# HexStepTroller_REV2auto.net
KiCad netlist of a schematic drawn in EAGLE
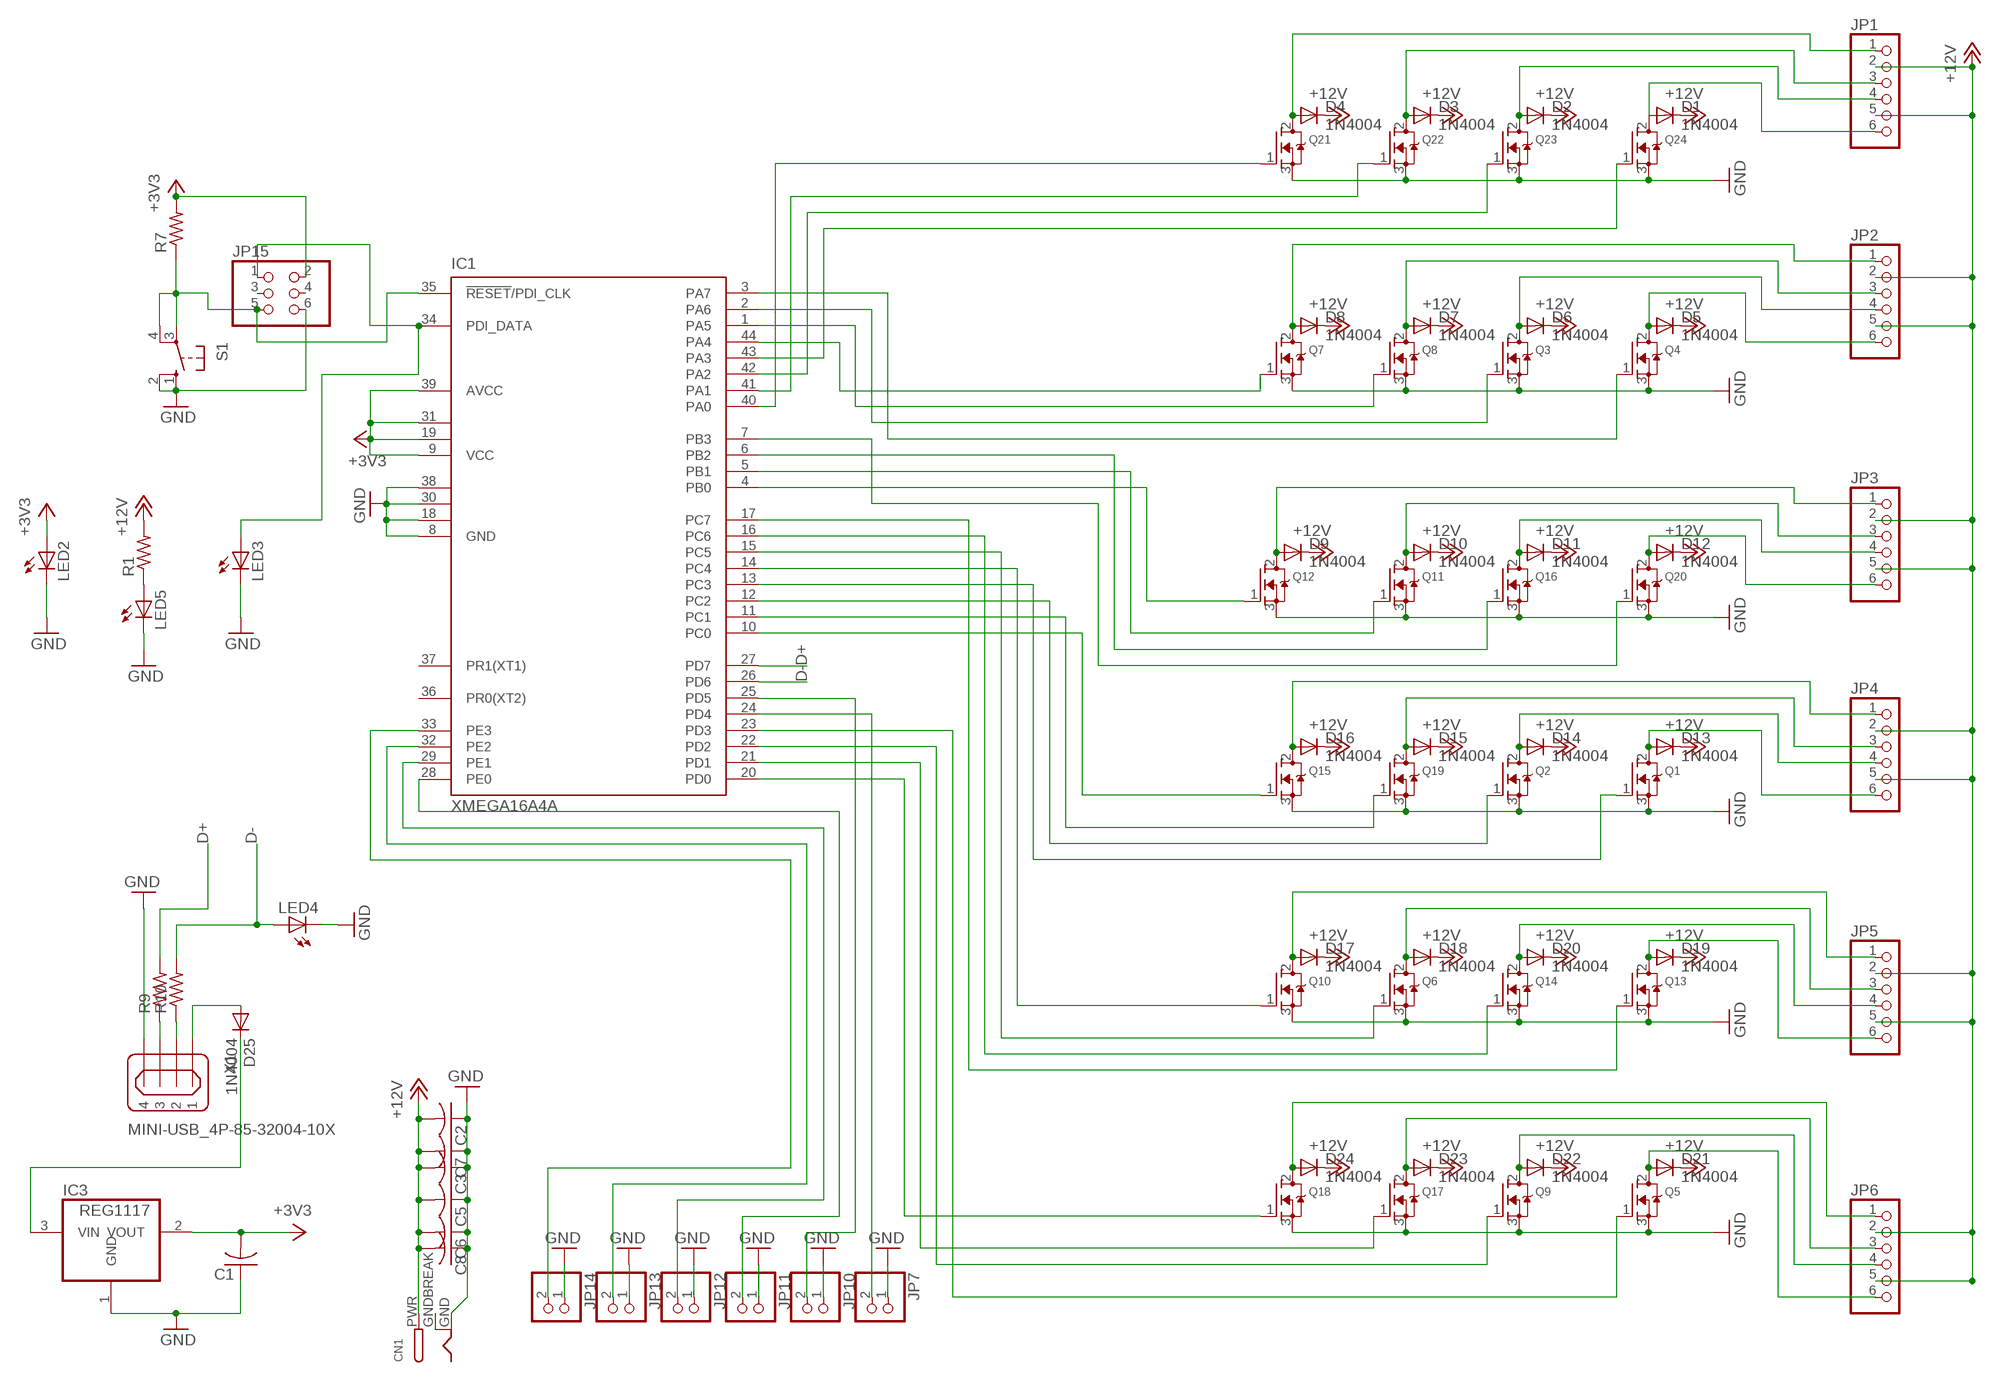
[diagram p0: schematic, sheet 1]

(export (version "E")
  (design (tool "Eeschema 10.0.6"))
  (components
    (comp (ref "C1")
      (value "C-US050-075X075")
      (footprint "eagle-import:C050-075X075")
      (libsource (lib "eagle-import") (part "C-US050-075X075"))
    )
    (comp (ref "C2")
      (value "C-US050-075X075")
      (footprint "eagle-import:C050-075X075")
      (libsource (lib "eagle-import") (part "C-US050-075X075"))
    )
    (comp (ref "C3")
      (value "C-US050-075X075")
      (footprint "eagle-import:C050-075X075")
      (libsource (lib "eagle-import") (part "C-US050-075X075"))
    )
    (comp (ref "C5")
      (value "C-US050-075X075")
      (footprint "eagle-import:C050-075X075")
      (libsource (lib "eagle-import") (part "C-US050-075X075"))
    )
    (comp (ref "C6")
      (value "C-US050-075X075")
      (footprint "eagle-import:C050-075X075")
      (libsource (lib "eagle-import") (part "C-US050-075X075"))
    )
    (comp (ref "C7")
      (value "C-US050-075X075")
      (footprint "eagle-import:C050-075X075")
      (libsource (lib "eagle-import") (part "C-US050-075X075"))
    )
    (comp (ref "C8")
      (value "C-US050-075X075")
      (footprint "eagle-import:C050-075X075")
      (libsource (lib "eagle-import") (part "C-US050-075X075"))
    )
    (comp (ref "CN1")
      (value "DCBARRELPTH")
      (footprint "eagle-import:DCJACK_2MM_PTH")
      (libsource (lib "eagle-import") (part "DCBARRELPTH"))
    )
    (comp (ref "D1")
      (value "1N4004")
      (footprint "eagle-import:DO41-10")
      (libsource (lib "eagle-import") (part "1N4004"))
    )
    (comp (ref "D2")
      (value "1N4004")
      (footprint "eagle-import:DO41-10")
      (libsource (lib "eagle-import") (part "1N4004"))
    )
    (comp (ref "D3")
      (value "1N4004")
      (footprint "eagle-import:DO41-10")
      (libsource (lib "eagle-import") (part "1N4004"))
    )
    (comp (ref "D4")
      (value "1N4004")
      (footprint "eagle-import:DO41-10")
      (libsource (lib "eagle-import") (part "1N4004"))
    )
    (comp (ref "D5")
      (value "1N4004")
      (footprint "eagle-import:DO41-10")
      (libsource (lib "eagle-import") (part "1N4004"))
    )
    (comp (ref "D6")
      (value "1N4004")
      (footprint "eagle-import:DO41-10")
      (libsource (lib "eagle-import") (part "1N4004"))
    )
    (comp (ref "D7")
      (value "1N4004")
      (footprint "eagle-import:DO41-10")
      (libsource (lib "eagle-import") (part "1N4004"))
    )
    (comp (ref "D8")
      (value "1N4004")
      (footprint "eagle-import:DO41-10")
      (libsource (lib "eagle-import") (part "1N4004"))
    )
    (comp (ref "D9")
      (value "1N4004")
      (footprint "eagle-import:DO41-10")
      (libsource (lib "eagle-import") (part "1N4004"))
    )
    (comp (ref "D10")
      (value "1N4004")
      (footprint "eagle-import:DO41-10")
      (libsource (lib "eagle-import") (part "1N4004"))
    )
    (comp (ref "D11")
      (value "1N4004")
      (footprint "eagle-import:DO41-10")
      (libsource (lib "eagle-import") (part "1N4004"))
    )
    (comp (ref "D12")
      (value "1N4004")
      (footprint "eagle-import:DO41-10")
      (libsource (lib "eagle-import") (part "1N4004"))
    )
    (comp (ref "D13")
      (value "1N4004")
      (footprint "eagle-import:DO41-10")
      (libsource (lib "eagle-import") (part "1N4004"))
    )
    (comp (ref "D14")
      (value "1N4004")
      (footprint "eagle-import:DO41-10")
      (libsource (lib "eagle-import") (part "1N4004"))
    )
    (comp (ref "D15")
      (value "1N4004")
      (footprint "eagle-import:DO41-10")
      (libsource (lib "eagle-import") (part "1N4004"))
    )
    (comp (ref "D16")
      (value "1N4004")
      (footprint "eagle-import:DO41-10")
      (libsource (lib "eagle-import") (part "1N4004"))
    )
    (comp (ref "D17")
      (value "1N4004")
      (footprint "eagle-import:DO41-10")
      (libsource (lib "eagle-import") (part "1N4004"))
    )
    (comp (ref "D18")
      (value "1N4004")
      (footprint "eagle-import:DO41-10")
      (libsource (lib "eagle-import") (part "1N4004"))
    )
    (comp (ref "D19")
      (value "1N4004")
      (footprint "eagle-import:DO41-10")
      (libsource (lib "eagle-import") (part "1N4004"))
    )
    (comp (ref "D20")
      (value "1N4004")
      (footprint "eagle-import:DO41-10")
      (libsource (lib "eagle-import") (part "1N4004"))
    )
    (comp (ref "D21")
      (value "1N4004")
      (footprint "eagle-import:DO41-10")
      (libsource (lib "eagle-import") (part "1N4004"))
    )
    (comp (ref "D22")
      (value "1N4004")
      (footprint "eagle-import:DO41-10")
      (libsource (lib "eagle-import") (part "1N4004"))
    )
    (comp (ref "D23")
      (value "1N4004")
      (footprint "eagle-import:DO41-10")
      (libsource (lib "eagle-import") (part "1N4004"))
    )
    (comp (ref "D24")
      (value "1N4004")
      (footprint "eagle-import:DO41-10")
      (libsource (lib "eagle-import") (part "1N4004"))
    )
    (comp (ref "D25")
      (value "1N4004")
      (footprint "eagle-import:DO41-10")
      (libsource (lib "eagle-import") (part "1N4004"))
    )
    (comp (ref "IC1")
      (value "XMEGA16A4A")
      (footprint "eagle-import:TQFP44")
      (libsource (lib "eagle-import") (part "XMEGA16A4A"))
    )
    (comp (ref "IC3")
      (value "REG1117")
      (footprint "eagle-import:SOT223")
      (libsource (lib "eagle-import") (part "REG1117"))
    )
    (comp (ref "JP1")
      (value "PINHD-1X6")
      (footprint "eagle-import:1X06")
      (libsource (lib "eagle-import") (part "PINHD-1X6"))
    )
    (comp (ref "JP2")
      (value "PINHD-1X6")
      (footprint "eagle-import:1X06")
      (libsource (lib "eagle-import") (part "PINHD-1X6"))
    )
    (comp (ref "JP3")
      (value "PINHD-1X6")
      (footprint "eagle-import:1X06")
      (libsource (lib "eagle-import") (part "PINHD-1X6"))
    )
    (comp (ref "JP4")
      (value "PINHD-1X6")
      (footprint "eagle-import:1X06")
      (libsource (lib "eagle-import") (part "PINHD-1X6"))
    )
    (comp (ref "JP5")
      (value "PINHD-1X6")
      (footprint "eagle-import:1X06")
      (libsource (lib "eagle-import") (part "PINHD-1X6"))
    )
    (comp (ref "JP6")
      (value "PINHD-1X6")
      (footprint "eagle-import:1X06")
      (libsource (lib "eagle-import") (part "PINHD-1X6"))
    )
    (comp (ref "JP7")
      (value "PINHD-1X2")
      (footprint "eagle-import:1X02")
      (libsource (lib "eagle-import") (part "PINHD-1X2"))
    )
    (comp (ref "JP10")
      (value "PINHD-1X2")
      (footprint "eagle-import:1X02")
      (libsource (lib "eagle-import") (part "PINHD-1X2"))
    )
    (comp (ref "JP11")
      (value "PINHD-1X2")
      (footprint "eagle-import:1X02")
      (libsource (lib "eagle-import") (part "PINHD-1X2"))
    )
    (comp (ref "JP12")
      (value "PINHD-1X2")
      (footprint "eagle-import:1X02")
      (libsource (lib "eagle-import") (part "PINHD-1X2"))
    )
    (comp (ref "JP13")
      (value "PINHD-1X2")
      (footprint "eagle-import:1X02")
      (libsource (lib "eagle-import") (part "PINHD-1X2"))
    )
    (comp (ref "JP14")
      (value "PINHD-1X2")
      (footprint "eagle-import:1X02")
      (libsource (lib "eagle-import") (part "PINHD-1X2"))
    )
    (comp (ref "JP15")
      (value "PINHD-2X3")
      (footprint "eagle-import:2X03")
      (libsource (lib "eagle-import") (part "PINHD-2X3"))
    )
    (comp (ref "LED2")
      (value "LED5MM")
      (footprint "eagle-import:LED5MM")
      (libsource (lib "eagle-import") (part "LED5MM"))
    )
    (comp (ref "LED3")
      (value "LED5MM")
      (footprint "eagle-import:LED5MM")
      (libsource (lib "eagle-import") (part "LED5MM"))
    )
    (comp (ref "LED4")
      (value "LED5MM")
      (footprint "eagle-import:LED5MM")
      (libsource (lib "eagle-import") (part "LED5MM"))
    )
    (comp (ref "LED5")
      (value "LED5MM")
      (footprint "eagle-import:LED5MM")
      (libsource (lib "eagle-import") (part "LED5MM"))
    )
    (comp (ref "Q1")
      (value "MOSFET-NGDS_TO220V")
      (footprint "eagle-import:TO220V")
      (libsource (lib "eagle-import") (part "MOSFET-NGDS_TO220V"))
    )
    (comp (ref "Q2")
      (value "MOSFET-NGDS_TO220V")
      (footprint "eagle-import:TO220V")
      (libsource (lib "eagle-import") (part "MOSFET-NGDS_TO220V"))
    )
    (comp (ref "Q3")
      (value "MOSFET-NGDS_TO220V")
      (footprint "eagle-import:TO220V")
      (libsource (lib "eagle-import") (part "MOSFET-NGDS_TO220V"))
    )
    (comp (ref "Q4")
      (value "MOSFET-NGDS_TO220V")
      (footprint "eagle-import:TO220V")
      (libsource (lib "eagle-import") (part "MOSFET-NGDS_TO220V"))
    )
    (comp (ref "Q5")
      (value "MOSFET-NGDS_TO220V")
      (footprint "eagle-import:TO220V")
      (libsource (lib "eagle-import") (part "MOSFET-NGDS_TO220V"))
    )
    (comp (ref "Q6")
      (value "MOSFET-NGDS_TO220V")
      (footprint "eagle-import:TO220V")
      (libsource (lib "eagle-import") (part "MOSFET-NGDS_TO220V"))
    )
    (comp (ref "Q7")
      (value "MOSFET-NGDS_TO220V")
      (footprint "eagle-import:TO220V")
      (libsource (lib "eagle-import") (part "MOSFET-NGDS_TO220V"))
    )
    (comp (ref "Q8")
      (value "MOSFET-NGDS_TO220V")
      (footprint "eagle-import:TO220V")
      (libsource (lib "eagle-import") (part "MOSFET-NGDS_TO220V"))
    )
    (comp (ref "Q9")
      (value "MOSFET-NGDS_TO220V")
      (footprint "eagle-import:TO220V")
      (libsource (lib "eagle-import") (part "MOSFET-NGDS_TO220V"))
    )
    (comp (ref "Q10")
      (value "MOSFET-NGDS_TO220V")
      (footprint "eagle-import:TO220V")
      (libsource (lib "eagle-import") (part "MOSFET-NGDS_TO220V"))
    )
    (comp (ref "Q11")
      (value "MOSFET-NGDS_TO220V")
      (footprint "eagle-import:TO220V")
      (libsource (lib "eagle-import") (part "MOSFET-NGDS_TO220V"))
    )
    (comp (ref "Q12")
      (value "MOSFET-NGDS_TO220V")
      (footprint "eagle-import:TO220V")
      (libsource (lib "eagle-import") (part "MOSFET-NGDS_TO220V"))
    )
    (comp (ref "Q13")
      (value "MOSFET-NGDS_TO220V")
      (footprint "eagle-import:TO220V")
      (libsource (lib "eagle-import") (part "MOSFET-NGDS_TO220V"))
    )
    (comp (ref "Q14")
      (value "MOSFET-NGDS_TO220V")
      (footprint "eagle-import:TO220V")
      (libsource (lib "eagle-import") (part "MOSFET-NGDS_TO220V"))
    )
    (comp (ref "Q15")
      (value "MOSFET-NGDS_TO220V")
      (footprint "eagle-import:TO220V")
      (libsource (lib "eagle-import") (part "MOSFET-NGDS_TO220V"))
    )
    (comp (ref "Q16")
      (value "MOSFET-NGDS_TO220V")
      (footprint "eagle-import:TO220V")
      (libsource (lib "eagle-import") (part "MOSFET-NGDS_TO220V"))
    )
    (comp (ref "Q17")
      (value "MOSFET-NGDS_TO220V")
      (footprint "eagle-import:TO220V")
      (libsource (lib "eagle-import") (part "MOSFET-NGDS_TO220V"))
    )
    (comp (ref "Q18")
      (value "MOSFET-NGDS_TO220V")
      (footprint "eagle-import:TO220V")
      (libsource (lib "eagle-import") (part "MOSFET-NGDS_TO220V"))
    )
    (comp (ref "Q19")
      (value "MOSFET-NGDS_TO220V")
      (footprint "eagle-import:TO220V")
      (libsource (lib "eagle-import") (part "MOSFET-NGDS_TO220V"))
    )
    (comp (ref "Q20")
      (value "MOSFET-NGDS_TO220V")
      (footprint "eagle-import:TO220V")
      (libsource (lib "eagle-import") (part "MOSFET-NGDS_TO220V"))
    )
    (comp (ref "Q21")
      (value "MOSFET-NGDS_TO220V")
      (footprint "eagle-import:TO220V")
      (libsource (lib "eagle-import") (part "MOSFET-NGDS_TO220V"))
    )
    (comp (ref "Q22")
      (value "MOSFET-NGDS_TO220V")
      (footprint "eagle-import:TO220V")
      (libsource (lib "eagle-import") (part "MOSFET-NGDS_TO220V"))
    )
    (comp (ref "Q23")
      (value "MOSFET-NGDS_TO220V")
      (footprint "eagle-import:TO220V")
      (libsource (lib "eagle-import") (part "MOSFET-NGDS_TO220V"))
    )
    (comp (ref "Q24")
      (value "MOSFET-NGDS_TO220V")
      (footprint "eagle-import:TO220V")
      (libsource (lib "eagle-import") (part "MOSFET-NGDS_TO220V"))
    )
    (comp (ref "R1")
      (value "R-US_0204/7")
      (footprint "eagle-import:0204_7")
      (libsource (lib "eagle-import") (part "R-US_0204/7"))
    )
    (comp (ref "R7")
      (value "R-US_0204/7")
      (footprint "eagle-import:0204_7")
      (libsource (lib "eagle-import") (part "R-US_0204/7"))
    )
    (comp (ref "R9")
      (value "R-US_0204/7")
      (footprint "eagle-import:0204_7")
      (libsource (lib "eagle-import") (part "R-US_0204/7"))
    )
    (comp (ref "R10")
      (value "R-US_0204/7")
      (footprint "eagle-import:0204_7")
      (libsource (lib "eagle-import") (part "R-US_0204/7"))
    )
    (comp (ref "S1")
      (value "10-XX")
      (footprint "eagle-import:B3F-10XX")
      (fields (field (name "MPN") "B3F-1000"))
      (libsource (lib "eagle-import") (part "10-XX"))
    )
    (comp (ref "X1")
      (value "MINI-USB_4P-85-32004-10X")
      (footprint "eagle-import:85-32004-10X")
      (libsource (lib "eagle-import") (part "MINI-USB_4P-85-32004-10X"))
    )
  )
  (nets
    (net (code "1") (name "+3V3") (class "Default")
      (node (ref "C1") (pin "2") (pinfunction "2_2") (pintype "passive"))
      (node (ref "IC1") (pin "19") (pinfunction "VCC1_19") (pintype "power_in"))
      (node (ref "IC1") (pin "31") (pinfunction "VCC2_31") (pintype "power_in"))
      (node (ref "IC1") (pin "39") (pinfunction "AVCC_39") (pintype "power_in"))
      (node (ref "IC1") (pin "9") (pinfunction "VCC_9") (pintype "power_in"))
      (node (ref "IC3") (pin "2") (pinfunction "VOUT_2") (pintype "output"))
      (node (ref "JP15") (pin "2") (pinfunction "2_2") (pintype "passive"))
      (node (ref "LED2") (pin "A") (pinfunction "A_A") (pintype "passive"))
      (node (ref "R7") (pin "2") (pinfunction "2_2") (pintype "passive"))
    )
    (net (code "2") (name "+12V") (class "Default")
      (node (ref "C2") (pin "2") (pinfunction "2_2") (pintype "passive"))
      (node (ref "C3") (pin "2") (pinfunction "2_2") (pintype "passive"))
      (node (ref "C5") (pin "2") (pinfunction "2_2") (pintype "passive"))
      (node (ref "C6") (pin "2") (pinfunction "2_2") (pintype "passive"))
      (node (ref "C7") (pin "2") (pinfunction "2_2") (pintype "passive"))
      (node (ref "C8") (pin "2") (pinfunction "2_2") (pintype "passive"))
      (node (ref "CN1") (pin "PWR") (pinfunction "PWR_PWR") (pintype "power_in"))
      (node (ref "D1") (pin "C") (pinfunction "C_C") (pintype "passive"))
      (node (ref "D10") (pin "C") (pinfunction "C_C") (pintype "passive"))
      (node (ref "D11") (pin "C") (pinfunction "C_C") (pintype "passive"))
      (node (ref "D12") (pin "C") (pinfunction "C_C") (pintype "passive"))
      (node (ref "D13") (pin "C") (pinfunction "C_C") (pintype "passive"))
      (node (ref "D14") (pin "C") (pinfunction "C_C") (pintype "passive"))
      (node (ref "D15") (pin "C") (pinfunction "C_C") (pintype "passive"))
      (node (ref "D16") (pin "C") (pinfunction "C_C") (pintype "passive"))
      (node (ref "D17") (pin "C") (pinfunction "C_C") (pintype "passive"))
      (node (ref "D18") (pin "C") (pinfunction "C_C") (pintype "passive"))
      (node (ref "D19") (pin "C") (pinfunction "C_C") (pintype "passive"))
      (node (ref "D2") (pin "C") (pinfunction "C_C") (pintype "passive"))
      (node (ref "D20") (pin "C") (pinfunction "C_C") (pintype "passive"))
      (node (ref "D21") (pin "C") (pinfunction "C_C") (pintype "passive"))
      (node (ref "D22") (pin "C") (pinfunction "C_C") (pintype "passive"))
      (node (ref "D23") (pin "C") (pinfunction "C_C") (pintype "passive"))
      (node (ref "D24") (pin "C") (pinfunction "C_C") (pintype "passive"))
      (node (ref "D3") (pin "C") (pinfunction "C_C") (pintype "passive"))
      (node (ref "D4") (pin "C") (pinfunction "C_C") (pintype "passive"))
      (node (ref "D5") (pin "C") (pinfunction "C_C") (pintype "passive"))
      (node (ref "D6") (pin "C") (pinfunction "C_C") (pintype "passive"))
      (node (ref "D7") (pin "C") (pinfunction "C_C") (pintype "passive"))
      (node (ref "D8") (pin "C") (pinfunction "C_C") (pintype "passive"))
      (node (ref "D9") (pin "C") (pinfunction "C_C") (pintype "passive"))
      (node (ref "JP1") (pin "2") (pinfunction "2_2") (pintype "passive"))
      (node (ref "JP1") (pin "5") (pinfunction "5_5") (pintype "passive"))
      (node (ref "JP2") (pin "2") (pinfunction "2_2") (pintype "passive"))
      (node (ref "JP2") (pin "5") (pinfunction "5_5") (pintype "passive"))
      (node (ref "JP3") (pin "2") (pinfunction "2_2") (pintype "passive"))
      (node (ref "JP3") (pin "5") (pinfunction "5_5") (pintype "passive"))
      (node (ref "JP4") (pin "2") (pinfunction "2_2") (pintype "passive"))
      (node (ref "JP4") (pin "5") (pinfunction "5_5") (pintype "passive"))
      (node (ref "JP5") (pin "2") (pinfunction "2_2") (pintype "passive"))
      (node (ref "JP5") (pin "5") (pinfunction "5_5") (pintype "passive"))
      (node (ref "JP6") (pin "2") (pinfunction "2_2") (pintype "passive"))
      (node (ref "JP6") (pin "5") (pinfunction "5_5") (pintype "passive"))
      (node (ref "R1") (pin "2") (pinfunction "2_2") (pintype "passive"))
    )
    (net (code "3") (name "/D+") (class "Default")
      (node (ref "IC1") (pin "27") (pinfunction "PD7_27") (pintype "bidirectional"))
      (node (ref "R9") (pin "2") (pinfunction "2_2") (pintype "passive"))
    )
    (net (code "4") (name "/D-") (class "Default")
      (node (ref "IC1") (pin "26") (pinfunction "PD6_26") (pintype "bidirectional"))
      (node (ref "LED4") (pin "A") (pinfunction "A_A") (pintype "passive"))
      (node (ref "R10") (pin "2") (pinfunction "2_2") (pintype "passive"))
    )
    (net (code "5") (name "/GNDBREAK") (class "Default")
      (node (ref "CN1") (pin "GNDBREAK") (pinfunction "GNDBREAK_GNDBREAK") (pintype "power_in"))
    )
    (net (code "6") (name "GND") (class "Default")
      (node (ref "C1") (pin "1") (pinfunction "1_1") (pintype "passive"))
      (node (ref "C2") (pin "1") (pinfunction "1_1") (pintype "passive"))
      (node (ref "C3") (pin "1") (pinfunction "1_1") (pintype "passive"))
      (node (ref "C5") (pin "1") (pinfunction "1_1") (pintype "passive"))
      (node (ref "C6") (pin "1") (pinfunction "1_1") (pintype "passive"))
      (node (ref "C7") (pin "1") (pinfunction "1_1") (pintype "passive"))
      (node (ref "C8") (pin "1") (pinfunction "1_1") (pintype "passive"))
      (node (ref "CN1") (pin "GND") (pinfunction "GND_GND") (pintype "power_in"))
      (node (ref "IC1") (pin "18") (pinfunction "GND1_18") (pintype "power_in"))
      (node (ref "IC1") (pin "30") (pinfunction "GND2_30") (pintype "power_in"))
      (node (ref "IC1") (pin "38") (pinfunction "GND3_38") (pintype "power_in"))
      (node (ref "IC1") (pin "8") (pinfunction "GND_8") (pintype "power_in"))
      (node (ref "IC3") (pin "1") (pinfunction "GND_1") (pintype "power_in"))
      (node (ref "JP10") (pin "1") (pinfunction "1_1") (pintype "passive"))
      (node (ref "JP11") (pin "1") (pinfunction "1_1") (pintype "passive"))
      (node (ref "JP12") (pin "1") (pinfunction "1_1") (pintype "passive"))
      (node (ref "JP13") (pin "1") (pinfunction "1_1") (pintype "passive"))
      (node (ref "JP14") (pin "1") (pinfunction "1_1") (pintype "passive"))
      (node (ref "JP15") (pin "6") (pinfunction "6_6") (pintype "passive"))
      (node (ref "JP7") (pin "1") (pinfunction "1_1") (pintype "passive"))
      (node (ref "LED2") (pin "K") (pinfunction "C_K") (pintype "passive"))
      (node (ref "LED3") (pin "K") (pinfunction "C_K") (pintype "passive"))
      (node (ref "LED4") (pin "K") (pinfunction "C_K") (pintype "passive"))
      (node (ref "LED5") (pin "K") (pinfunction "C_K") (pintype "passive"))
      (node (ref "Q1") (pin "3") (pinfunction "S_3") (pintype "bidirectional"))
      (node (ref "Q10") (pin "3") (pinfunction "S_3") (pintype "bidirectional"))
      (node (ref "Q11") (pin "3") (pinfunction "S_3") (pintype "bidirectional"))
      (node (ref "Q12") (pin "3") (pinfunction "S_3") (pintype "bidirectional"))
      (node (ref "Q13") (pin "3") (pinfunction "S_3") (pintype "bidirectional"))
      (node (ref "Q14") (pin "3") (pinfunction "S_3") (pintype "bidirectional"))
      (node (ref "Q15") (pin "3") (pinfunction "S_3") (pintype "bidirectional"))
      (node (ref "Q16") (pin "3") (pinfunction "S_3") (pintype "bidirectional"))
      (node (ref "Q17") (pin "3") (pinfunction "S_3") (pintype "bidirectional"))
      (node (ref "Q18") (pin "3") (pinfunction "S_3") (pintype "bidirectional"))
      (node (ref "Q19") (pin "3") (pinfunction "S_3") (pintype "bidirectional"))
      (node (ref "Q2") (pin "3") (pinfunction "S_3") (pintype "bidirectional"))
      (node (ref "Q20") (pin "3") (pinfunction "S_3") (pintype "bidirectional"))
      (node (ref "Q21") (pin "3") (pinfunction "S_3") (pintype "bidirectional"))
      (node (ref "Q22") (pin "3") (pinfunction "S_3") (pintype "bidirectional"))
      (node (ref "Q23") (pin "3") (pinfunction "S_3") (pintype "bidirectional"))
      (node (ref "Q24") (pin "3") (pinfunction "S_3") (pintype "bidirectional"))
      (node (ref "Q3") (pin "3") (pinfunction "S_3") (pintype "bidirectional"))
      (node (ref "Q4") (pin "3") (pinfunction "S_3") (pintype "bidirectional"))
      (node (ref "Q5") (pin "3") (pinfunction "S_3") (pintype "bidirectional"))
      (node (ref "Q6") (pin "3") (pinfunction "S_3") (pintype "bidirectional"))
      (node (ref "Q7") (pin "3") (pinfunction "S_3") (pintype "bidirectional"))
      (node (ref "Q8") (pin "3") (pinfunction "S_3") (pintype "bidirectional"))
      (node (ref "Q9") (pin "3") (pinfunction "S_3") (pintype "bidirectional"))
      (node (ref "S1") (pin "1") (pinfunction "S_1") (pintype "passive"))
      (node (ref "S1") (pin "2") (pinfunction "S1_2") (pintype "passive"))
      (node (ref "X1") (pin "4") (pinfunction "4_4") (pintype "passive"))
    )
    (net (code "7") (name "Net-(D25-PadA)") (class "Default")
      (node (ref "D25") (pin "A") (pinfunction "A_A") (pintype "passive"))
      (node (ref "X1") (pin "1") (pinfunction "1_1") (pintype "passive"))
    )
    (net (code "8") (name "Net-(IC1-PA0)") (class "Default")
      (node (ref "IC1") (pin "40") (pinfunction "PA0_40") (pintype "bidirectional"))
      (node (ref "Q21") (pin "1") (pinfunction "G_1") (pintype "bidirectional"))
    )
    (net (code "9") (name "Net-(IC1-PA1)") (class "Default")
      (node (ref "IC1") (pin "41") (pinfunction "PA1_41") (pintype "bidirectional"))
      (node (ref "Q22") (pin "1") (pinfunction "G_1") (pintype "bidirectional"))
    )
    (net (code "10") (name "Net-(IC1-PA2)") (class "Default")
      (node (ref "IC1") (pin "42") (pinfunction "PA2_42") (pintype "bidirectional"))
      (node (ref "Q23") (pin "1") (pinfunction "G_1") (pintype "bidirectional"))
    )
    (net (code "11") (name "Net-(IC1-PA3)") (class "Default")
      (node (ref "IC1") (pin "43") (pinfunction "PA3_43") (pintype "bidirectional"))
      (node (ref "Q24") (pin "1") (pinfunction "G_1") (pintype "bidirectional"))
    )
    (net (code "12") (name "Net-(IC1-PA4)") (class "Default")
      (node (ref "IC1") (pin "44") (pinfunction "PA4_44") (pintype "bidirectional"))
      (node (ref "Q7") (pin "1") (pinfunction "G_1") (pintype "bidirectional"))
    )
    (net (code "13") (name "Net-(IC1-PA5)") (class "Default")
      (node (ref "IC1") (pin "1") (pinfunction "PA5_1") (pintype "bidirectional"))
      (node (ref "Q8") (pin "1") (pinfunction "G_1") (pintype "bidirectional"))
    )
    (net (code "14") (name "Net-(IC1-PA6)") (class "Default")
      (node (ref "IC1") (pin "2") (pinfunction "PA6_2") (pintype "bidirectional"))
      (node (ref "Q3") (pin "1") (pinfunction "G_1") (pintype "bidirectional"))
    )
    (net (code "15") (name "Net-(IC1-PA7)") (class "Default")
      (node (ref "IC1") (pin "3") (pinfunction "PA7_3") (pintype "bidirectional"))
      (node (ref "Q4") (pin "1") (pinfunction "G_1") (pintype "bidirectional"))
    )
    (net (code "16") (name "Net-(IC1-PB0)") (class "Default")
      (node (ref "IC1") (pin "4") (pinfunction "PB0_4") (pintype "bidirectional"))
      (node (ref "Q12") (pin "1") (pinfunction "G_1") (pintype "bidirectional"))
    )
    (net (code "17") (name "Net-(IC1-PB1)") (class "Default")
      (node (ref "IC1") (pin "5") (pinfunction "PB1_5") (pintype "bidirectional"))
      (node (ref "Q11") (pin "1") (pinfunction "G_1") (pintype "bidirectional"))
    )
    (net (code "18") (name "Net-(IC1-PB2)") (class "Default")
      (node (ref "IC1") (pin "6") (pinfunction "PB2_6") (pintype "bidirectional"))
      (node (ref "Q16") (pin "1") (pinfunction "G_1") (pintype "bidirectional"))
    )
    (net (code "19") (name "Net-(IC1-PB3)") (class "Default")
      (node (ref "IC1") (pin "7") (pinfunction "PB3_7") (pintype "bidirectional"))
      (node (ref "Q20") (pin "1") (pinfunction "G_1") (pintype "bidirectional"))
    )
    (net (code "20") (name "Net-(IC1-PC0)") (class "Default")
      (node (ref "IC1") (pin "10") (pinfunction "PC0_10") (pintype "bidirectional"))
      (node (ref "Q15") (pin "1") (pinfunction "G_1") (pintype "bidirectional"))
    )
    (net (code "21") (name "Net-(IC1-PC1)") (class "Default")
      (node (ref "IC1") (pin "11") (pinfunction "PC1_11") (pintype "bidirectional"))
      (node (ref "Q19") (pin "1") (pinfunction "G_1") (pintype "bidirectional"))
    )
    (net (code "22") (name "Net-(IC1-PC2)") (class "Default")
      (node (ref "IC1") (pin "12") (pinfunction "PC2_12") (pintype "bidirectional"))
      (node (ref "Q2") (pin "1") (pinfunction "G_1") (pintype "bidirectional"))
    )
    (net (code "23") (name "Net-(IC1-PC3)") (class "Default")
      (node (ref "IC1") (pin "13") (pinfunction "PC3_13") (pintype "bidirectional"))
      (node (ref "Q1") (pin "1") (pinfunction "G_1") (pintype "bidirectional"))
    )
    (net (code "24") (name "Net-(IC1-PC4)") (class "Default")
      (node (ref "IC1") (pin "14") (pinfunction "PC4_14") (pintype "bidirectional"))
      (node (ref "Q10") (pin "1") (pinfunction "G_1") (pintype "bidirectional"))
    )
    (net (code "25") (name "Net-(IC1-PC5)") (class "Default")
      (node (ref "IC1") (pin "15") (pinfunction "PC5_15") (pintype "bidirectional"))
      (node (ref "Q6") (pin "1") (pinfunction "G_1") (pintype "bidirectional"))
    )
    (net (code "26") (name "Net-(IC1-PC6)") (class "Default")
      (node (ref "IC1") (pin "16") (pinfunction "PC6_16") (pintype "bidirectional"))
      (node (ref "Q14") (pin "1") (pinfunction "G_1") (pintype "bidirectional"))
    )
    (net (code "27") (name "Net-(IC1-PC7)") (class "Default")
      (node (ref "IC1") (pin "17") (pinfunction "PC7_17") (pintype "bidirectional"))
      (node (ref "Q13") (pin "1") (pinfunction "G_1") (pintype "bidirectional"))
    )
    (net (code "28") (name "Net-(IC1-PD0)") (class "Default")
      (node (ref "IC1") (pin "20") (pinfunction "PD0_20") (pintype "bidirectional"))
      (node (ref "Q18") (pin "1") (pinfunction "G_1") (pintype "bidirectional"))
    )
    (net (code "29") (name "Net-(IC1-PD1)") (class "Default")
      (node (ref "IC1") (pin "21") (pinfunction "PD1_21") (pintype "bidirectional"))
      (node (ref "Q17") (pin "1") (pinfunction "G_1") (pintype "bidirectional"))
    )
    (net (code "30") (name "Net-(IC1-PD2)") (class "Default")
      (node (ref "IC1") (pin "22") (pinfunction "PD2_22") (pintype "bidirectional"))
      (node (ref "Q9") (pin "1") (pinfunction "G_1") (pintype "bidirectional"))
    )
    (net (code "31") (name "Net-(IC1-PD3)") (class "Default")
      (node (ref "IC1") (pin "23") (pinfunction "PD3_23") (pintype "bidirectional"))
      (node (ref "Q5") (pin "1") (pinfunction "G_1") (pintype "bidirectional"))
    )
    (net (code "32") (name "Net-(IC1-PD4)") (class "Default")
      (node (ref "IC1") (pin "24") (pinfunction "PD4_24") (pintype "bidirectional"))
      (node (ref "JP7") (pin "2") (pinfunction "2_2") (pintype "passive"))
    )
    (net (code "33") (name "Net-(IC1-PD5)") (class "Default")
      (node (ref "IC1") (pin "25") (pinfunction "PD5_25") (pintype "bidirectional"))
      (node (ref "JP10") (pin "2") (pinfunction "2_2") (pintype "passive"))
    )
    (net (code "34") (name "Net-(IC1-PDI_DATA)") (class "Default")
      (node (ref "IC1") (pin "34") (pinfunction "PDI_DATA_34") (pintype "bidirectional"))
      (node (ref "JP15") (pin "1") (pinfunction "1_1") (pintype "passive"))
      (node (ref "LED3") (pin "A") (pinfunction "A_A") (pintype "passive"))
    )
    (net (code "35") (name "Net-(IC1-PE0)") (class "Default")
      (node (ref "IC1") (pin "28") (pinfunction "PE0_28") (pintype "bidirectional"))
      (node (ref "JP11") (pin "2") (pinfunction "2_2") (pintype "passive"))
    )
    (net (code "36") (name "Net-(IC1-PE1)") (class "Default")
      (node (ref "IC1") (pin "29") (pinfunction "PE1_29") (pintype "bidirectional"))
      (node (ref "JP12") (pin "2") (pinfunction "2_2") (pintype "passive"))
    )
    (net (code "37") (name "Net-(IC1-PE2)") (class "Default")
      (node (ref "IC1") (pin "32") (pinfunction "PE2_32") (pintype "bidirectional"))
      (node (ref "JP13") (pin "2") (pinfunction "2_2") (pintype "passive"))
    )
    (net (code "38") (name "Net-(IC1-PE3)") (class "Default")
      (node (ref "IC1") (pin "33") (pinfunction "PE3_33") (pintype "bidirectional"))
      (node (ref "JP14") (pin "2") (pinfunction "2_2") (pintype "passive"))
    )
    (net (code "39") (name "Net-(IC1-~{RESET}{slash}PDI_CLK)") (class "Default")
      (node (ref "IC1") (pin "35") (pinfunction "~{RESET}/PDI_CLK_35") (pintype "bidirectional"))
      (node (ref "JP15") (pin "5") (pinfunction "5_5") (pintype "passive"))
      (node (ref "R7") (pin "1") (pinfunction "1_1") (pintype "passive"))
      (node (ref "S1") (pin "3") (pinfunction "P_3") (pintype "passive"))
      (node (ref "S1") (pin "4") (pinfunction "P1_4") (pintype "passive"))
    )
    (net (code "40") (name "Net-(IC3-VIN)") (class "Default")
      (node (ref "D25") (pin "C") (pinfunction "C_C") (pintype "passive"))
      (node (ref "IC3") (pin "3") (pinfunction "VIN_3") (pintype "input"))
    )
    (net (code "41") (name "Net-(LED5-PadA)") (class "Default")
      (node (ref "LED5") (pin "A") (pinfunction "A_A") (pintype "passive"))
      (node (ref "R1") (pin "1") (pinfunction "1_1") (pintype "passive"))
    )
    (net (code "42") (name "Net-(Q1-D)") (class "Default")
      (node (ref "D13") (pin "A") (pinfunction "A_A") (pintype "passive"))
      (node (ref "JP4") (pin "6") (pinfunction "6_6") (pintype "passive"))
      (node (ref "Q1") (pin "2") (pinfunction "D_2") (pintype "bidirectional"))
    )
    (net (code "43") (name "Net-(Q2-D)") (class "Default")
      (node (ref "D14") (pin "A") (pinfunction "A_A") (pintype "passive"))
      (node (ref "JP4") (pin "4") (pinfunction "4_4") (pintype "passive"))
      (node (ref "Q2") (pin "2") (pinfunction "D_2") (pintype "bidirectional"))
    )
    (net (code "44") (name "Net-(Q3-D)") (class "Default")
      (node (ref "D6") (pin "A") (pinfunction "A_A") (pintype "passive"))
      (node (ref "JP2") (pin "4") (pinfunction "4_4") (pintype "passive"))
      (node (ref "Q3") (pin "2") (pinfunction "D_2") (pintype "bidirectional"))
    )
    (net (code "45") (name "Net-(Q4-D)") (class "Default")
      (node (ref "D5") (pin "A") (pinfunction "A_A") (pintype "passive"))
      (node (ref "JP2") (pin "6") (pinfunction "6_6") (pintype "passive"))
      (node (ref "Q4") (pin "2") (pinfunction "D_2") (pintype "bidirectional"))
    )
    (net (code "46") (name "Net-(Q5-D)") (class "Default")
      (node (ref "D21") (pin "A") (pinfunction "A_A") (pintype "passive"))
      (node (ref "JP6") (pin "6") (pinfunction "6_6") (pintype "passive"))
      (node (ref "Q5") (pin "2") (pinfunction "D_2") (pintype "bidirectional"))
    )
    (net (code "47") (name "Net-(Q6-D)") (class "Default")
      (node (ref "D18") (pin "A") (pinfunction "A_A") (pintype "passive"))
      (node (ref "JP5") (pin "3") (pinfunction "3_3") (pintype "passive"))
      (node (ref "Q6") (pin "2") (pinfunction "D_2") (pintype "bidirectional"))
    )
    (net (code "48") (name "Net-(Q7-D)") (class "Default")
      (node (ref "D8") (pin "A") (pinfunction "A_A") (pintype "passive"))
      (node (ref "JP2") (pin "1") (pinfunction "1_1") (pintype "passive"))
      (node (ref "Q7") (pin "2") (pinfunction "D_2") (pintype "bidirectional"))
    )
    (net (code "49") (name "Net-(Q8-D)") (class "Default")
      (node (ref "D7") (pin "A") (pinfunction "A_A") (pintype "passive"))
      (node (ref "JP2") (pin "3") (pinfunction "3_3") (pintype "passive"))
      (node (ref "Q8") (pin "2") (pinfunction "D_2") (pintype "bidirectional"))
    )
    (net (code "50") (name "Net-(Q9-D)") (class "Default")
      (node (ref "D22") (pin "A") (pinfunction "A_A") (pintype "passive"))
      (node (ref "JP6") (pin "4") (pinfunction "4_4") (pintype "passive"))
      (node (ref "Q9") (pin "2") (pinfunction "D_2") (pintype "bidirectional"))
    )
    (net (code "51") (name "Net-(Q10-D)") (class "Default")
      (node (ref "D17") (pin "A") (pinfunction "A_A") (pintype "passive"))
      (node (ref "JP5") (pin "1") (pinfunction "1_1") (pintype "passive"))
      (node (ref "Q10") (pin "2") (pinfunction "D_2") (pintype "bidirectional"))
    )
    (net (code "52") (name "Net-(Q11-D)") (class "Default")
      (node (ref "D10") (pin "A") (pinfunction "A_A") (pintype "passive"))
      (node (ref "JP3") (pin "3") (pinfunction "3_3") (pintype "passive"))
      (node (ref "Q11") (pin "2") (pinfunction "D_2") (pintype "bidirectional"))
    )
    (net (code "53") (name "Net-(Q12-D)") (class "Default")
      (node (ref "D9") (pin "A") (pinfunction "A_A") (pintype "passive"))
      (node (ref "JP3") (pin "1") (pinfunction "1_1") (pintype "passive"))
      (node (ref "Q12") (pin "2") (pinfunction "D_2") (pintype "bidirectional"))
    )
    (net (code "54") (name "Net-(Q13-D)") (class "Default")
      (node (ref "D19") (pin "A") (pinfunction "A_A") (pintype "passive"))
      (node (ref "JP5") (pin "6") (pinfunction "6_6") (pintype "passive"))
      (node (ref "Q13") (pin "2") (pinfunction "D_2") (pintype "bidirectional"))
    )
    (net (code "55") (name "Net-(Q14-D)") (class "Default")
      (node (ref "D20") (pin "A") (pinfunction "A_A") (pintype "passive"))
      (node (ref "JP5") (pin "4") (pinfunction "4_4") (pintype "passive"))
      (node (ref "Q14") (pin "2") (pinfunction "D_2") (pintype "bidirectional"))
    )
    (net (code "56") (name "Net-(Q15-D)") (class "Default")
      (node (ref "D16") (pin "A") (pinfunction "A_A") (pintype "passive"))
      (node (ref "JP4") (pin "1") (pinfunction "1_1") (pintype "passive"))
      (node (ref "Q15") (pin "2") (pinfunction "D_2") (pintype "bidirectional"))
    )
    (net (code "57") (name "Net-(Q16-D)") (class "Default")
      (node (ref "D11") (pin "A") (pinfunction "A_A") (pintype "passive"))
      (node (ref "JP3") (pin "4") (pinfunction "4_4") (pintype "passive"))
      (node (ref "Q16") (pin "2") (pinfunction "D_2") (pintype "bidirectional"))
    )
    (net (code "58") (name "Net-(Q17-D)") (class "Default")
      (node (ref "D23") (pin "A") (pinfunction "A_A") (pintype "passive"))
      (node (ref "JP6") (pin "3") (pinfunction "3_3") (pintype "passive"))
      (node (ref "Q17") (pin "2") (pinfunction "D_2") (pintype "bidirectional"))
    )
    (net (code "59") (name "Net-(Q18-D)") (class "Default")
      (node (ref "D24") (pin "A") (pinfunction "A_A") (pintype "passive"))
      (node (ref "JP6") (pin "1") (pinfunction "1_1") (pintype "passive"))
      (node (ref "Q18") (pin "2") (pinfunction "D_2") (pintype "bidirectional"))
    )
    (net (code "60") (name "Net-(Q19-D)") (class "Default")
      (node (ref "D15") (pin "A") (pinfunction "A_A") (pintype "passive"))
      (node (ref "JP4") (pin "3") (pinfunction "3_3") (pintype "passive"))
      (node (ref "Q19") (pin "2") (pinfunction "D_2") (pintype "bidirectional"))
    )
    (net (code "61") (name "Net-(Q20-D)") (class "Default")
      (node (ref "D12") (pin "A") (pinfunction "A_A") (pintype "passive"))
      (node (ref "JP3") (pin "6") (pinfunction "6_6") (pintype "passive"))
      (node (ref "Q20") (pin "2") (pinfunction "D_2") (pintype "bidirectional"))
    )
    (net (code "62") (name "Net-(Q21-D)") (class "Default")
      (node (ref "D4") (pin "A") (pinfunction "A_A") (pintype "passive"))
      (node (ref "JP1") (pin "1") (pinfunction "1_1") (pintype "passive"))
      (node (ref "Q21") (pin "2") (pinfunction "D_2") (pintype "bidirectional"))
    )
    (net (code "63") (name "Net-(Q22-D)") (class "Default")
      (node (ref "D3") (pin "A") (pinfunction "A_A") (pintype "passive"))
      (node (ref "JP1") (pin "3") (pinfunction "3_3") (pintype "passive"))
      (node (ref "Q22") (pin "2") (pinfunction "D_2") (pintype "bidirectional"))
    )
    (net (code "64") (name "Net-(Q23-D)") (class "Default")
      (node (ref "D2") (pin "A") (pinfunction "A_A") (pintype "passive"))
      (node (ref "JP1") (pin "4") (pinfunction "4_4") (pintype "passive"))
      (node (ref "Q23") (pin "2") (pinfunction "D_2") (pintype "bidirectional"))
    )
    (net (code "65") (name "Net-(Q24-D)") (class "Default")
      (node (ref "D1") (pin "A") (pinfunction "A_A") (pintype "passive"))
      (node (ref "JP1") (pin "6") (pinfunction "6_6") (pintype "passive"))
      (node (ref "Q24") (pin "2") (pinfunction "D_2") (pintype "bidirectional"))
    )
    (net (code "66") (name "Net-(R9-Pad1)") (class "Default")
      (node (ref "R9") (pin "1") (pinfunction "1_1") (pintype "passive"))
      (node (ref "X1") (pin "3") (pinfunction "3_3") (pintype "passive"))
    )
    (net (code "67") (name "Net-(R10-Pad1)") (class "Default")
      (node (ref "R10") (pin "1") (pinfunction "1_1") (pintype "passive"))
      (node (ref "X1") (pin "2") (pinfunction "2_2") (pintype "passive"))
    )
    (net (code "68") (name "unconnected-(IC1-PR0(XT2)-Pad36)") (class "Default")
      (node (ref "IC1") (pin "36") (pinfunction "PR0(XT2)_36") (pintype "bidirectional"))
    )
    (net (code "69") (name "unconnected-(IC1-PR1(XT1)-Pad37)") (class "Default")
      (node (ref "IC1") (pin "37") (pinfunction "PR1(XT1)_37") (pintype "bidirectional"))
    )
    (net (code "70") (name "unconnected-(JP15-Pad3)") (class "Default")
      (node (ref "JP15") (pin "3") (pinfunction "3_3") (pintype "passive"))
    )
    (net (code "71") (name "unconnected-(JP15-Pad4)") (class "Default")
      (node (ref "JP15") (pin "4") (pinfunction "4_4") (pintype "passive"))
    )
  )
)
